# H05.net
KiCad netlist of a schematic drawn in EAGLE
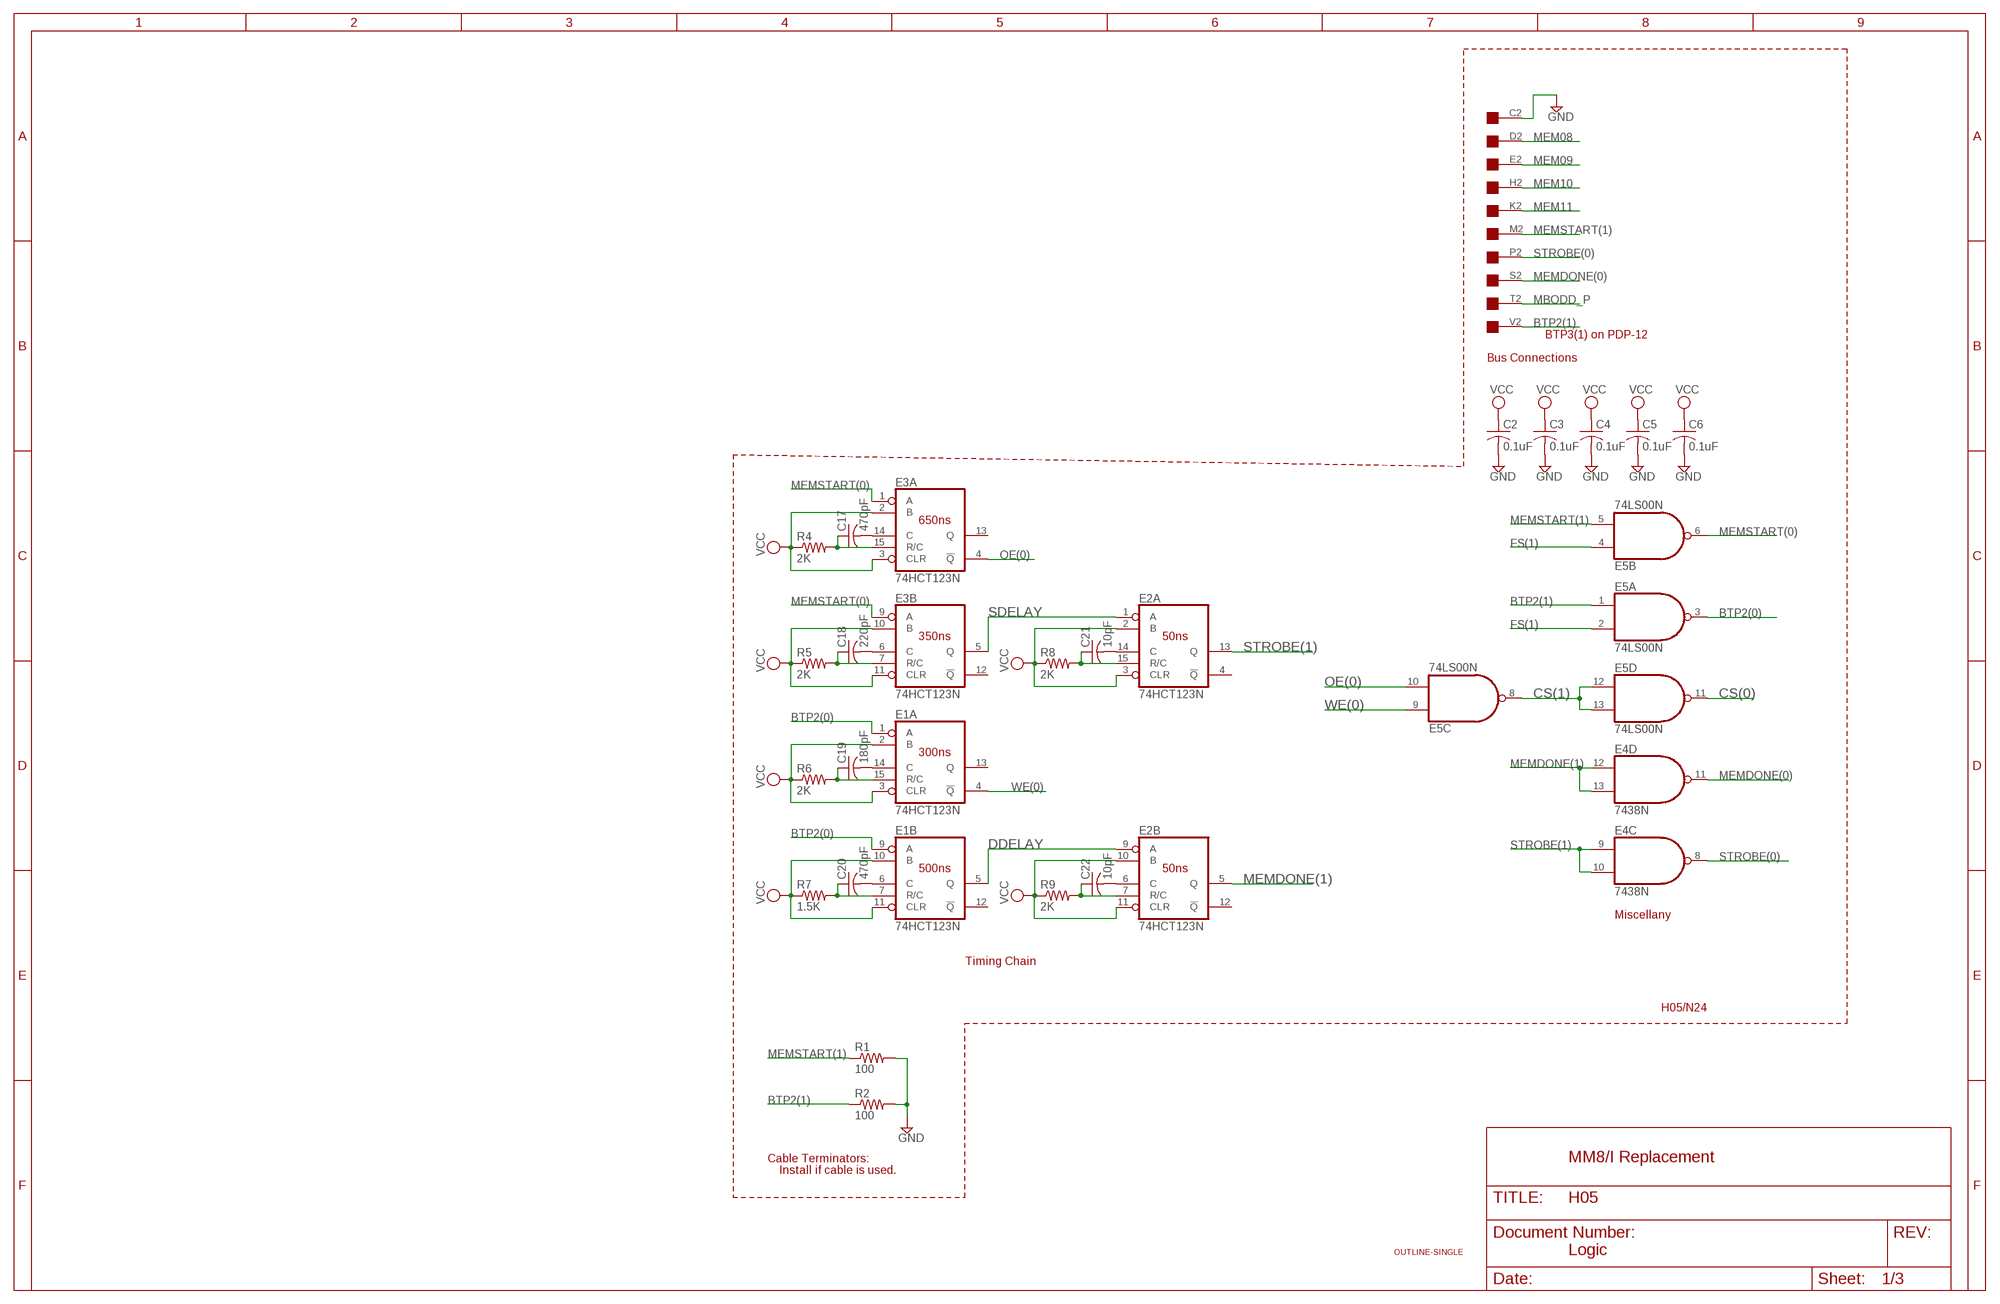
[diagram p0: schematic, sheet 1]
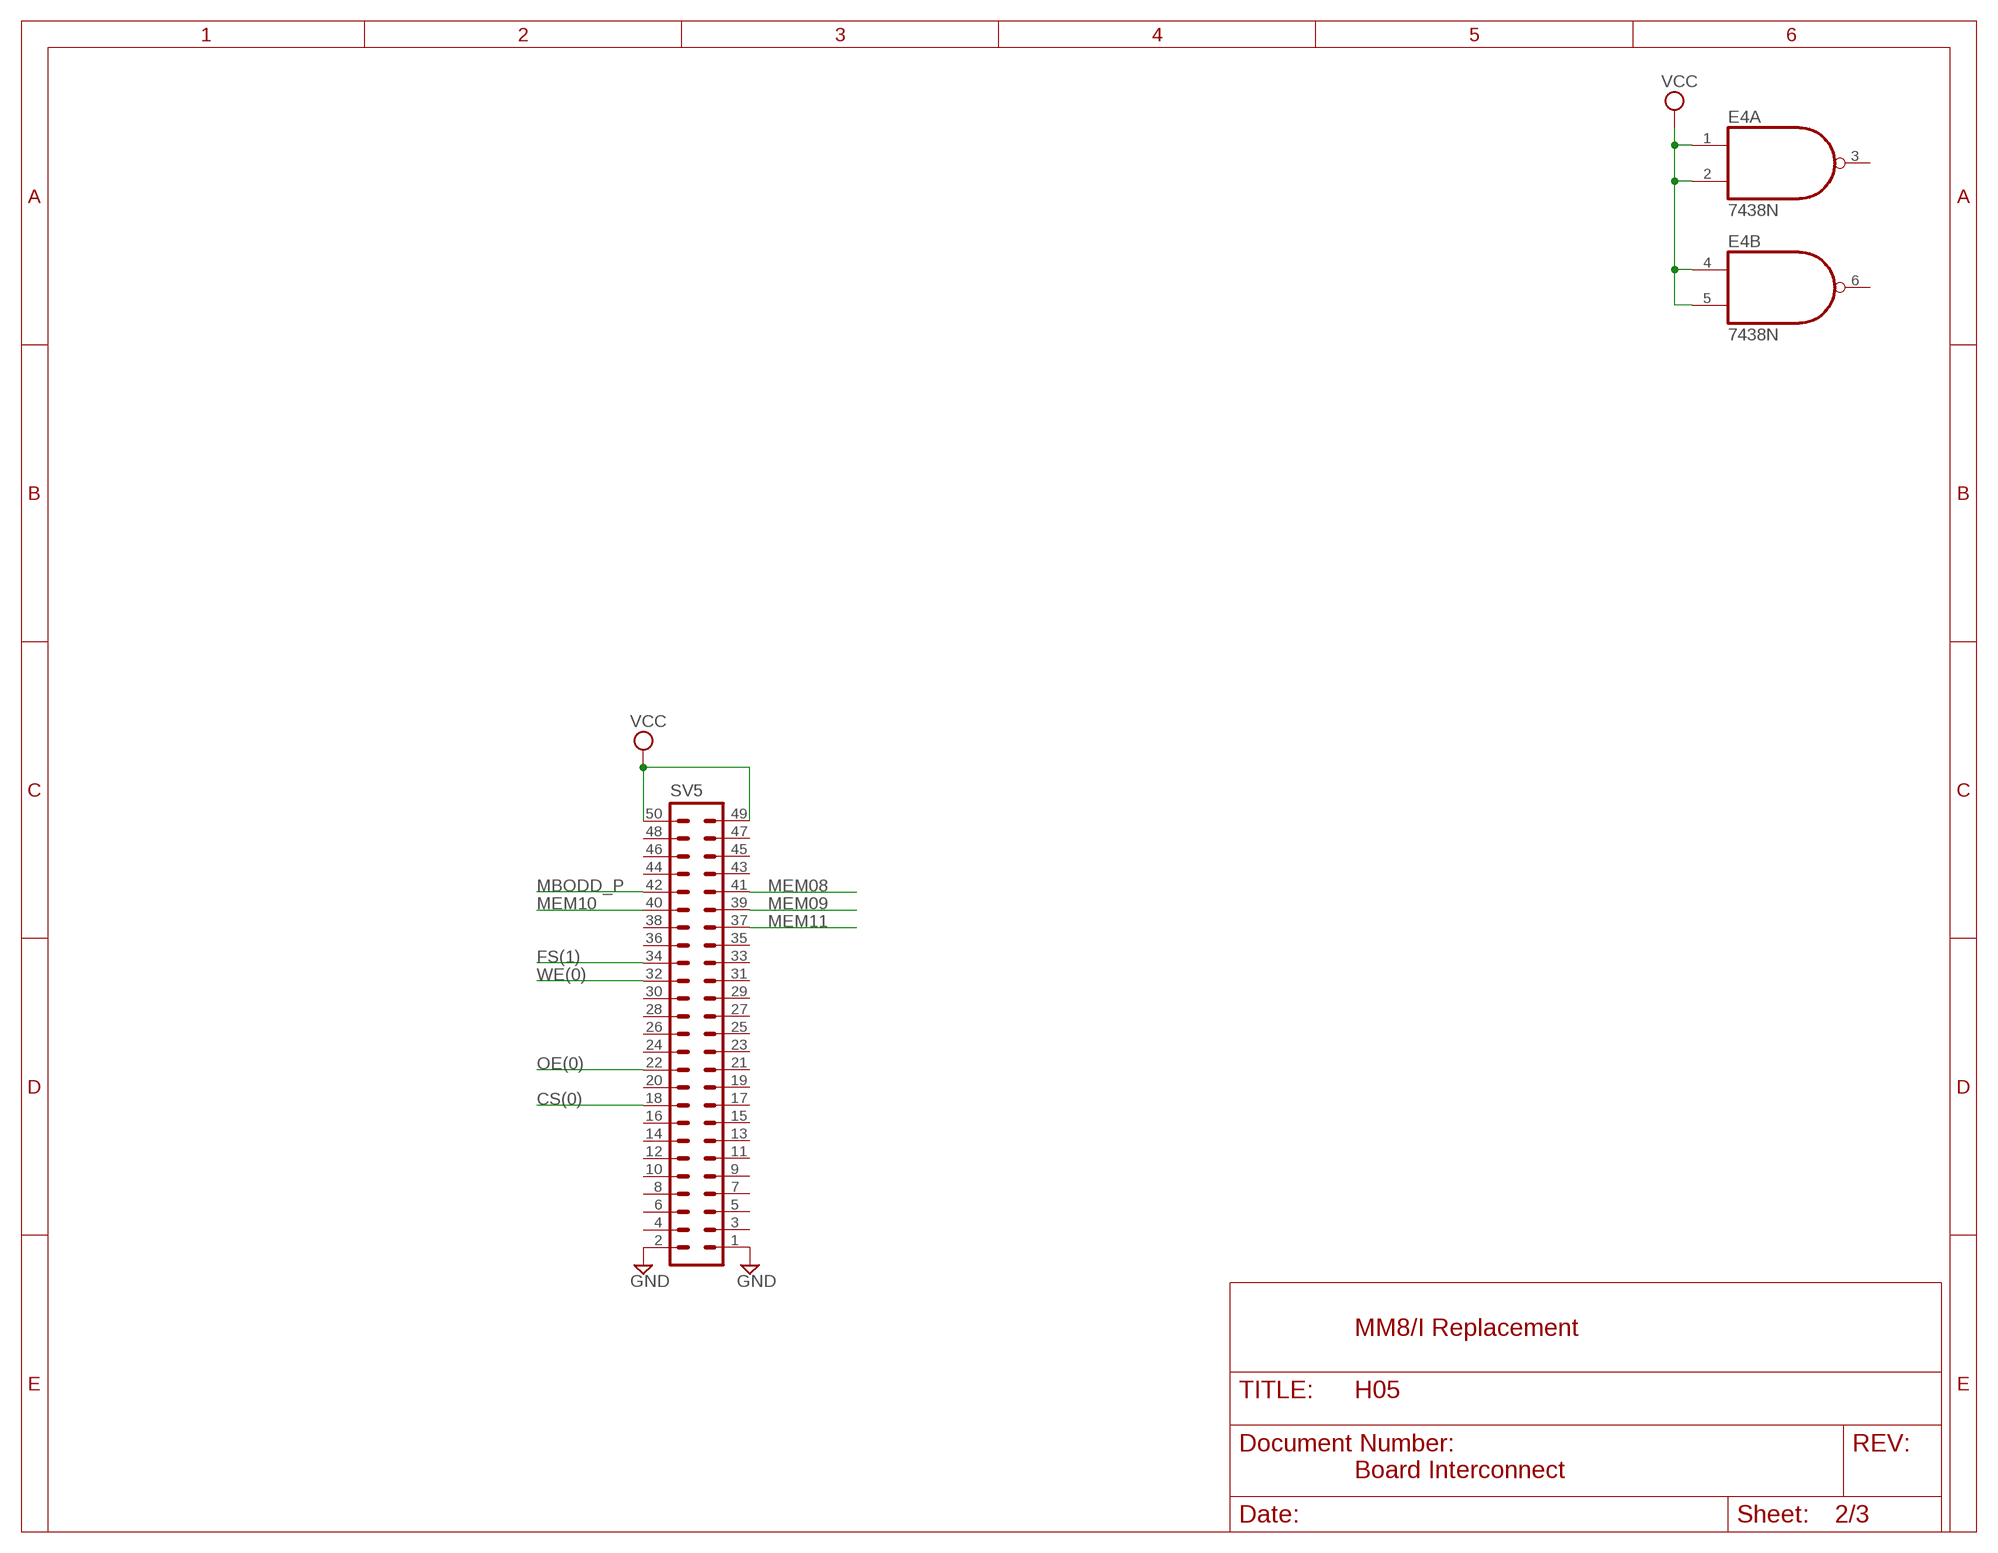
[diagram p1: schematic, sheet 2]
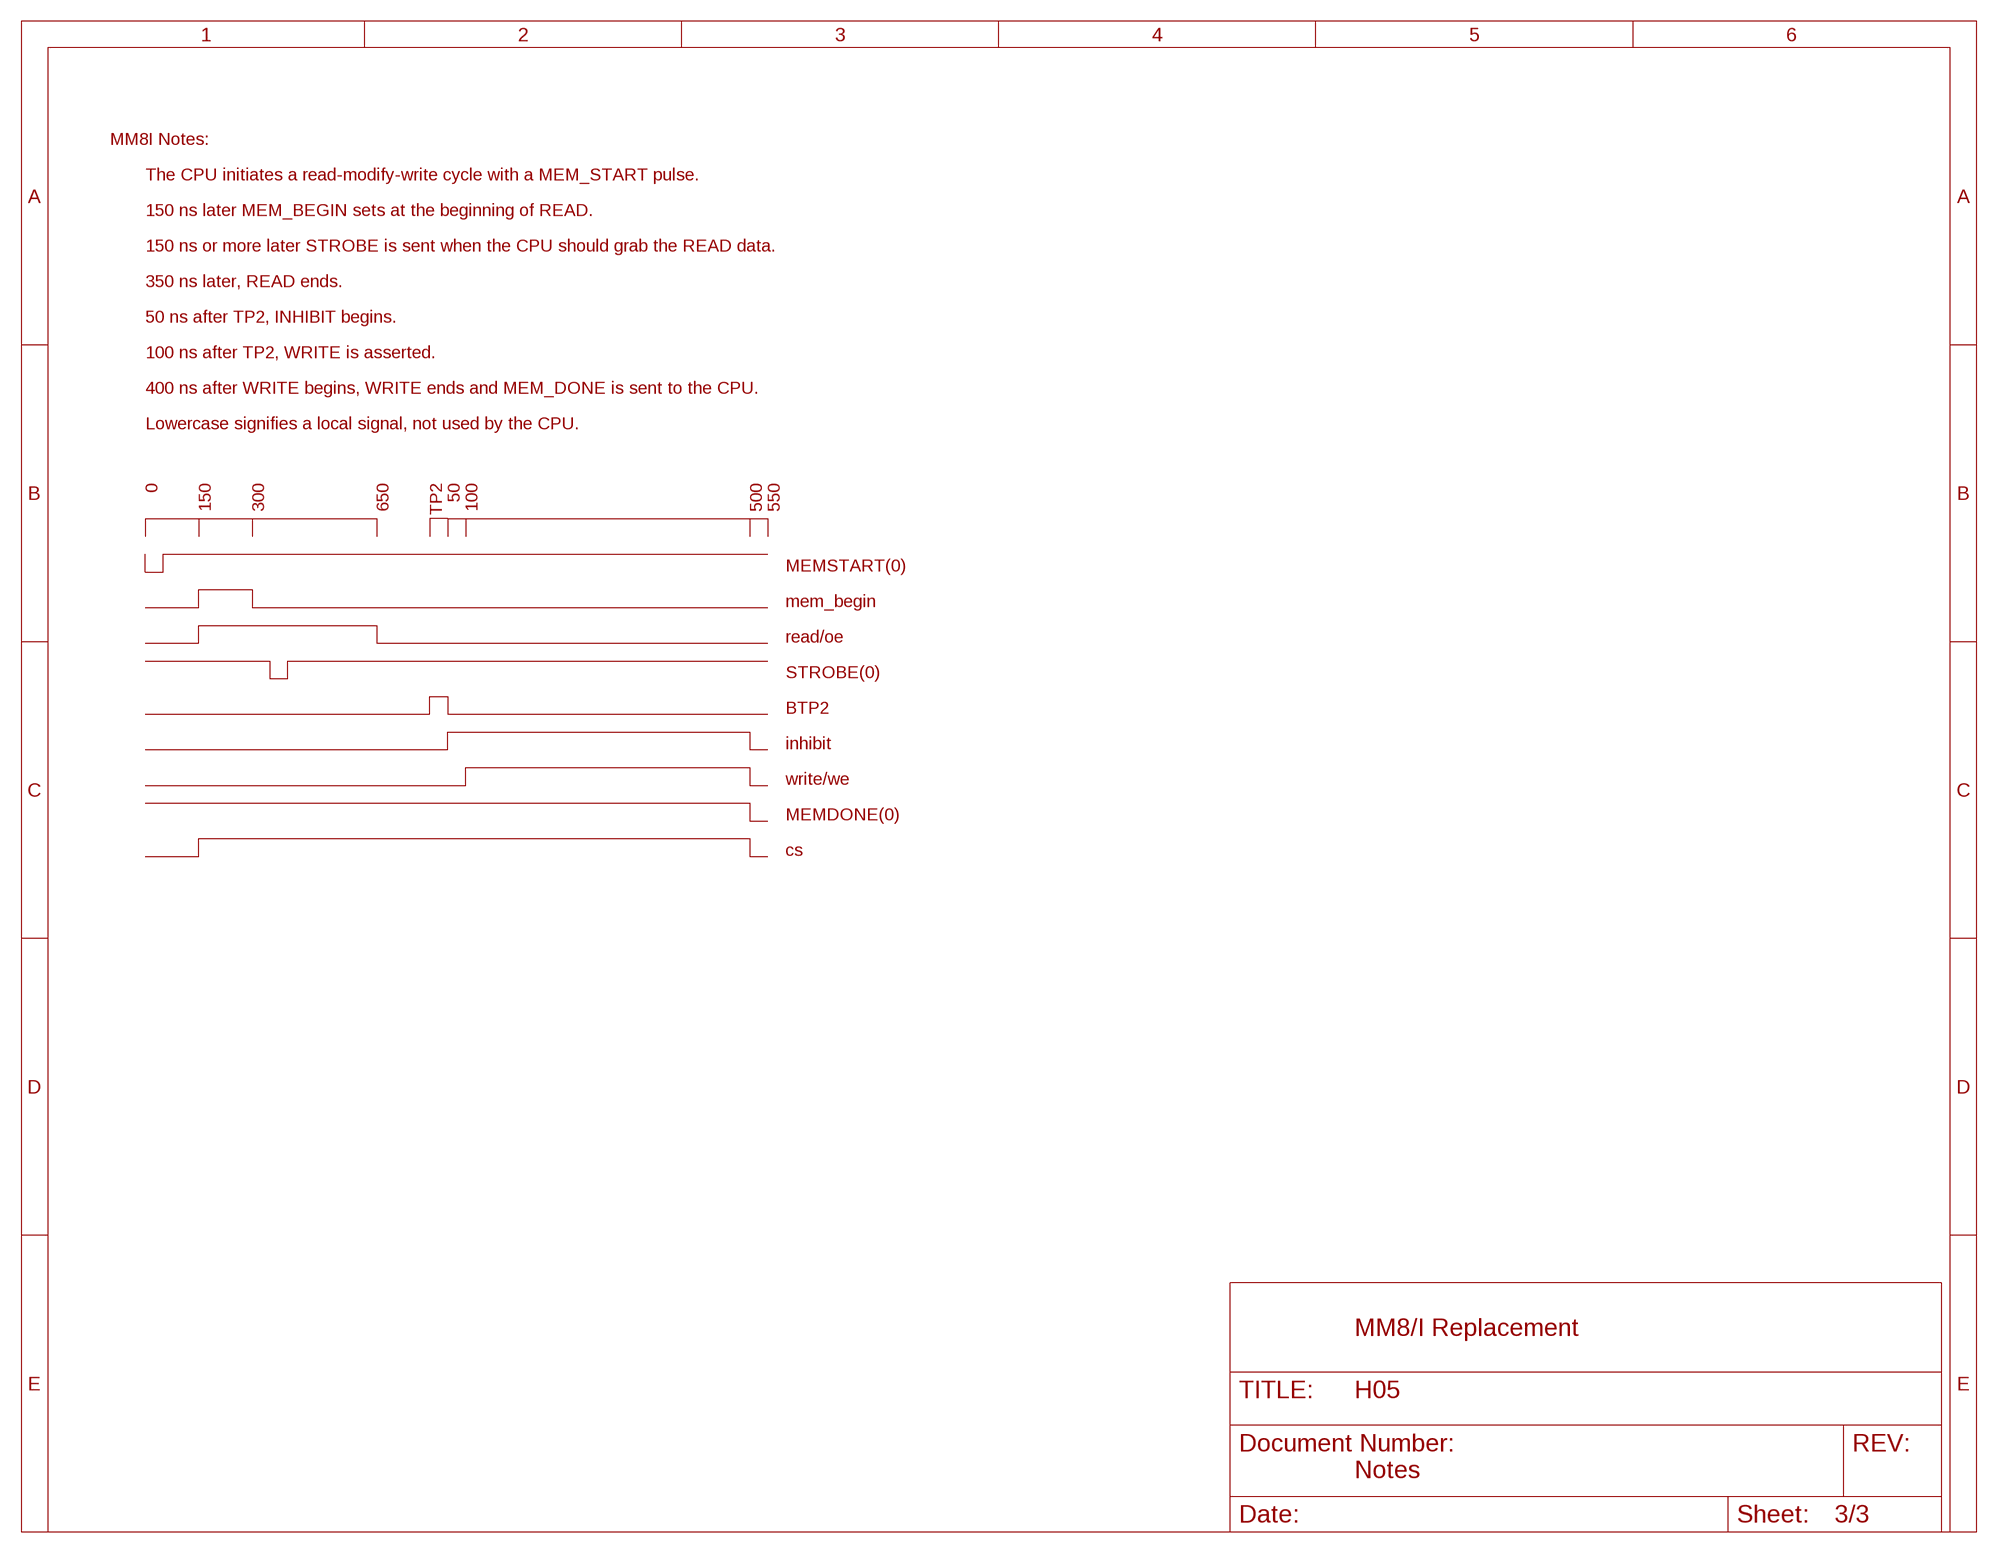
[diagram p2: schematic, sheet 3]

(export (version "E")
  (design (tool "Eeschema 10.0.6"))
  (components
    (comp (ref "C2")
      (value "0.1uF")
      (footprint "eagle-import:C050-025X075")
      (libsource (lib "eagle-import") (part "C-US050-025X075"))
    )
    (comp (ref "C3")
      (value "0.1uF")
      (footprint "eagle-import:C050-025X075")
      (libsource (lib "eagle-import") (part "C-US050-025X075"))
    )
    (comp (ref "C4")
      (value "0.1uF")
      (footprint "eagle-import:C050-025X075")
      (libsource (lib "eagle-import") (part "C-US050-025X075"))
    )
    (comp (ref "C5")
      (value "0.1uF")
      (footprint "eagle-import:C050-025X075")
      (libsource (lib "eagle-import") (part "C-US050-025X075"))
    )
    (comp (ref "C6")
      (value "0.1uF")
      (footprint "eagle-import:C050-025X075")
      (libsource (lib "eagle-import") (part "C-US050-025X075"))
    )
    (comp (ref "C17")
      (value "470pF")
      (footprint "eagle-import:C050-025X075")
      (libsource (lib "eagle-import") (part "C-US050-025X075"))
    )
    (comp (ref "C18")
      (value "220pF")
      (footprint "eagle-import:C050-025X075")
      (libsource (lib "eagle-import") (part "C-US050-025X075"))
    )
    (comp (ref "C19")
      (value "180pF")
      (footprint "eagle-import:C050-025X075")
      (libsource (lib "eagle-import") (part "C-US050-025X075"))
    )
    (comp (ref "C20")
      (value "470pF")
      (footprint "eagle-import:C050-025X075")
      (libsource (lib "eagle-import") (part "C-US050-025X075"))
    )
    (comp (ref "C21")
      (value "10pF")
      (footprint "eagle-import:C050-025X075")
      (libsource (lib "eagle-import") (part "C-US050-025X075"))
    )
    (comp (ref "C22")
      (value "10pF")
      (footprint "eagle-import:C050-025X075")
      (libsource (lib "eagle-import") (part "C-US050-025X075"))
    )
    (comp (ref "E1")
      (value "74HCT123N")
      (footprint "eagle-import:DIL16")
      (libsource (lib "eagle-import") (part "74123NLS"))
    )
    (comp (ref "E2")
      (value "74HCT123N")
      (footprint "eagle-import:DIL16")
      (libsource (lib "eagle-import") (part "74123NLS"))
    )
    (comp (ref "E3")
      (value "74HCT123N")
      (footprint "eagle-import:DIL16")
      (libsource (lib "eagle-import") (part "74123NLS"))
    )
    (comp (ref "E4")
      (value "7438N")
      (footprint "eagle-import:DIL14")
      (libsource (lib "eagle-import") (part "7438NLS"))
    )
    (comp (ref "E5")
      (value "74LS00N")
      (footprint "eagle-import:DIL14")
      (libsource (lib "eagle-import") (part "7400NLS"))
    )
    (comp (ref "H05")
      (value "EDGE-1")
      (footprint "eagle-import:EDGE-CON1")
      (libsource (lib "eagle-import") (part "EDGE-1"))
    )
    (comp (ref "R1")
      (value "100")
      (footprint "eagle-import:0207_10")
      (libsource (lib "eagle-import") (part "R-US_0207/10"))
    )
    (comp (ref "R2")
      (value "100")
      (footprint "eagle-import:0207_10")
      (libsource (lib "eagle-import") (part "R-US_0207/10"))
    )
    (comp (ref "R4")
      (value "2K")
      (footprint "eagle-import:0207_10")
      (libsource (lib "eagle-import") (part "R-US_0207/10"))
    )
    (comp (ref "R5")
      (value "2K")
      (footprint "eagle-import:0207_10")
      (libsource (lib "eagle-import") (part "R-US_0207/10"))
    )
    (comp (ref "R6")
      (value "2K")
      (footprint "eagle-import:0207_10")
      (libsource (lib "eagle-import") (part "R-US_0207/10"))
    )
    (comp (ref "R7")
      (value "1.5K")
      (footprint "eagle-import:0207_10")
      (libsource (lib "eagle-import") (part "R-US_0207/10"))
    )
    (comp (ref "R8")
      (value "2K")
      (footprint "eagle-import:0207_10")
      (libsource (lib "eagle-import") (part "R-US_0207/10"))
    )
    (comp (ref "R9")
      (value "2K")
      (footprint "eagle-import:0207_10")
      (libsource (lib "eagle-import") (part "R-US_0207/10"))
    )
    (comp (ref "U$1")
      (value "OUTLINE-SINGLE")
      (footprint "eagle-import:SINGLE")
      (libsource (lib "eagle-import") (part "OUTLINE-SINGLE"))
    )
    (comp (ref "SV5")
      (value "ML50L")
      (footprint "eagle-import:ML50L")
      (libsource (lib "eagle-import") (part "ML50L"))
    )
  )
  (nets
    (net (code "1") (name "BTP2(0)") (class "Default")
      (node (ref "E1") (pin "1") (pinfunction "A_1") (pintype "input"))
      (node (ref "E1") (pin "9") (pinfunction "A_9") (pintype "input"))
      (node (ref "E5") (pin "3") (pinfunction "O_3") (pintype "output"))
    )
    (net (code "2") (name "BTP2(1)") (class "Default")
      (node (ref "E5") (pin "1") (pinfunction "I0_1") (pintype "input"))
      (node (ref "H05") (pin "V2") (pinfunction "1_V2") (pintype "bidirectional"))
      (node (ref "R2") (pin "1") (pinfunction "1_1") (pintype "passive"))
    )
    (net (code "3") (name "CS(0)") (class "Default")
      (node (ref "E5") (pin "11") (pinfunction "O_11") (pintype "output"))
      (node (ref "SV5") (pin "18") (pinfunction "18_18") (pintype "passive"))
    )
    (net (code "4") (name "CS(1)") (class "Default")
      (node (ref "E5") (pin "12") (pinfunction "I0_12") (pintype "input"))
      (node (ref "E5") (pin "13") (pinfunction "I1_13") (pintype "input"))
      (node (ref "E5") (pin "8") (pinfunction "O_8") (pintype "output"))
    )
    (net (code "5") (name "DDELAY") (class "Default")
      (node (ref "E1") (pin "5") (pinfunction "Q_5") (pintype "output"))
      (node (ref "E2") (pin "9") (pinfunction "A_9") (pintype "input"))
    )
    (net (code "6") (name "FS(1)") (class "Default")
      (node (ref "E5") (pin "2") (pinfunction "I1_2") (pintype "input"))
      (node (ref "E5") (pin "4") (pinfunction "I0_4") (pintype "input"))
      (node (ref "SV5") (pin "34") (pinfunction "34_34") (pintype "passive"))
    )
    (net (code "7") (name "GND") (class "Default")
      (node (ref "C2") (pin "2") (pinfunction "2_2") (pintype "passive"))
      (node (ref "C3") (pin "2") (pinfunction "2_2") (pintype "passive"))
      (node (ref "C4") (pin "2") (pinfunction "2_2") (pintype "passive"))
      (node (ref "C5") (pin "2") (pinfunction "2_2") (pintype "passive"))
      (node (ref "C6") (pin "2") (pinfunction "2_2") (pintype "passive"))
      (node (ref "H05") (pin "C2") (pinfunction "1_C2") (pintype "bidirectional"))
      (node (ref "R1") (pin "2") (pinfunction "2_2") (pintype "passive"))
      (node (ref "R2") (pin "2") (pinfunction "2_2") (pintype "passive"))
      (node (ref "SV5") (pin "1") (pinfunction "1_1") (pintype "passive"))
      (node (ref "SV5") (pin "2") (pinfunction "2_2") (pintype "passive"))
    )
    (net (code "8") (name "MBODD_P") (class "Default")
      (node (ref "H05") (pin "T2") (pinfunction "1_T2") (pintype "bidirectional"))
      (node (ref "SV5") (pin "42") (pinfunction "42_42") (pintype "passive"))
    )
    (net (code "9") (name "MEM08") (class "Default")
      (node (ref "H05") (pin "D2") (pinfunction "1_D2") (pintype "bidirectional"))
      (node (ref "SV5") (pin "41") (pinfunction "41_41") (pintype "passive"))
    )
    (net (code "10") (name "MEM09") (class "Default")
      (node (ref "H05") (pin "E2") (pinfunction "1_E2") (pintype "bidirectional"))
      (node (ref "SV5") (pin "39") (pinfunction "39_39") (pintype "passive"))
    )
    (net (code "11") (name "MEM10") (class "Default")
      (node (ref "H05") (pin "H2") (pinfunction "1_H2") (pintype "bidirectional"))
      (node (ref "SV5") (pin "40") (pinfunction "40_40") (pintype "passive"))
    )
    (net (code "12") (name "MEM11") (class "Default")
      (node (ref "H05") (pin "K2") (pinfunction "1_K2") (pintype "bidirectional"))
      (node (ref "SV5") (pin "37") (pinfunction "37_37") (pintype "passive"))
    )
    (net (code "13") (name "MEMDONE(0)") (class "Default")
      (node (ref "E4") (pin "11") (pinfunction "O_11") (pintype "open_collector"))
      (node (ref "H05") (pin "S2") (pinfunction "1_S2") (pintype "bidirectional"))
    )
    (net (code "14") (name "MEMDONE(1)") (class "Default")
      (node (ref "E2") (pin "5") (pinfunction "Q_5") (pintype "output"))
      (node (ref "E4") (pin "12") (pinfunction "I0_12") (pintype "input"))
      (node (ref "E4") (pin "13") (pinfunction "I1_13") (pintype "input"))
    )
    (net (code "15") (name "MEMSTART(0)") (class "Default")
      (node (ref "E3") (pin "1") (pinfunction "A_1") (pintype "input"))
      (node (ref "E3") (pin "9") (pinfunction "A_9") (pintype "input"))
      (node (ref "E5") (pin "6") (pinfunction "O_6") (pintype "output"))
    )
    (net (code "16") (name "MEMSTART(1)") (class "Default")
      (node (ref "E5") (pin "5") (pinfunction "I1_5") (pintype "input"))
      (node (ref "H05") (pin "M2") (pinfunction "1_M2") (pintype "bidirectional"))
      (node (ref "R1") (pin "1") (pinfunction "1_1") (pintype "passive"))
    )
    (net (code "17") (name "Net-(E1A-C)") (class "Default")
      (node (ref "C19") (pin "2") (pinfunction "2_2") (pintype "passive"))
      (node (ref "E1") (pin "14") (pinfunction "C_14") (pintype "input"))
    )
    (net (code "18") (name "Net-(E1A-R{slash}C)") (class "Default")
      (node (ref "C19") (pin "1") (pinfunction "1_1") (pintype "passive"))
      (node (ref "E1") (pin "15") (pinfunction "R/C_15") (pintype "input"))
      (node (ref "R6") (pin "2") (pinfunction "2_2") (pintype "passive"))
    )
    (net (code "19") (name "Net-(E1B-C)") (class "Default")
      (node (ref "C20") (pin "2") (pinfunction "2_2") (pintype "passive"))
      (node (ref "E1") (pin "6") (pinfunction "C_6") (pintype "input"))
    )
    (net (code "20") (name "Net-(E1B-R{slash}C)") (class "Default")
      (node (ref "C20") (pin "1") (pinfunction "1_1") (pintype "passive"))
      (node (ref "E1") (pin "7") (pinfunction "R/C_7") (pintype "input"))
      (node (ref "R7") (pin "2") (pinfunction "2_2") (pintype "passive"))
    )
    (net (code "21") (name "Net-(E2A-C)") (class "Default")
      (node (ref "C21") (pin "2") (pinfunction "2_2") (pintype "passive"))
      (node (ref "E2") (pin "14") (pinfunction "C_14") (pintype "input"))
    )
    (net (code "22") (name "Net-(E2A-R{slash}C)") (class "Default")
      (node (ref "C21") (pin "1") (pinfunction "1_1") (pintype "passive"))
      (node (ref "E2") (pin "15") (pinfunction "R/C_15") (pintype "input"))
      (node (ref "R8") (pin "2") (pinfunction "2_2") (pintype "passive"))
    )
    (net (code "23") (name "Net-(E2B-C)") (class "Default")
      (node (ref "C22") (pin "2") (pinfunction "2_2") (pintype "passive"))
      (node (ref "E2") (pin "6") (pinfunction "C_6") (pintype "input"))
    )
    (net (code "24") (name "Net-(E2B-R{slash}C)") (class "Default")
      (node (ref "C22") (pin "1") (pinfunction "1_1") (pintype "passive"))
      (node (ref "E2") (pin "7") (pinfunction "R/C_7") (pintype "input"))
      (node (ref "R9") (pin "2") (pinfunction "2_2") (pintype "passive"))
    )
    (net (code "25") (name "Net-(E3A-C)") (class "Default")
      (node (ref "C17") (pin "2") (pinfunction "2_2") (pintype "passive"))
      (node (ref "E3") (pin "14") (pinfunction "C_14") (pintype "input"))
    )
    (net (code "26") (name "Net-(E3A-R{slash}C)") (class "Default")
      (node (ref "C17") (pin "1") (pinfunction "1_1") (pintype "passive"))
      (node (ref "E3") (pin "15") (pinfunction "R/C_15") (pintype "input"))
      (node (ref "R4") (pin "2") (pinfunction "2_2") (pintype "passive"))
    )
    (net (code "27") (name "Net-(E3B-C)") (class "Default")
      (node (ref "C18") (pin "2") (pinfunction "2_2") (pintype "passive"))
      (node (ref "E3") (pin "6") (pinfunction "C_6") (pintype "input"))
    )
    (net (code "28") (name "Net-(E3B-R{slash}C)") (class "Default")
      (node (ref "C18") (pin "1") (pinfunction "1_1") (pintype "passive"))
      (node (ref "E3") (pin "7") (pinfunction "R/C_7") (pintype "input"))
      (node (ref "R5") (pin "2") (pinfunction "2_2") (pintype "passive"))
    )
    (net (code "29") (name "OE(0)") (class "Default")
      (node (ref "E3") (pin "4") (pinfunction "~{Q}_4") (pintype "output"))
      (node (ref "E5") (pin "10") (pinfunction "I1_10") (pintype "input"))
      (node (ref "SV5") (pin "22") (pinfunction "22_22") (pintype "passive"))
    )
    (net (code "30") (name "SDELAY") (class "Default")
      (node (ref "E2") (pin "1") (pinfunction "A_1") (pintype "input"))
      (node (ref "E3") (pin "5") (pinfunction "Q_5") (pintype "output"))
    )
    (net (code "31") (name "STROBE(0)") (class "Default")
      (node (ref "E4") (pin "8") (pinfunction "O_8") (pintype "open_collector"))
      (node (ref "H05") (pin "P2") (pinfunction "1_P2") (pintype "bidirectional"))
    )
    (net (code "32") (name "STROBE(1)") (class "Default")
      (node (ref "E2") (pin "13") (pinfunction "Q_13") (pintype "output"))
      (node (ref "E4") (pin "10") (pinfunction "I1_10") (pintype "input"))
      (node (ref "E4") (pin "9") (pinfunction "I0_9") (pintype "input"))
    )
    (net (code "33") (name "VCC") (class "Default")
      (node (ref "C2") (pin "1") (pinfunction "1_1") (pintype "passive"))
      (node (ref "C3") (pin "1") (pinfunction "1_1") (pintype "passive"))
      (node (ref "C4") (pin "1") (pinfunction "1_1") (pintype "passive"))
      (node (ref "C5") (pin "1") (pinfunction "1_1") (pintype "passive"))
      (node (ref "C6") (pin "1") (pinfunction "1_1") (pintype "passive"))
      (node (ref "E1") (pin "10") (pinfunction "B_10") (pintype "input"))
      (node (ref "E1") (pin "11") (pinfunction "CLR_11") (pintype "input"))
      (node (ref "E1") (pin "2") (pinfunction "B_2") (pintype "input"))
      (node (ref "E1") (pin "3") (pinfunction "CLR_3") (pintype "input"))
      (node (ref "E2") (pin "10") (pinfunction "B_10") (pintype "input"))
      (node (ref "E2") (pin "11") (pinfunction "CLR_11") (pintype "input"))
      (node (ref "E2") (pin "2") (pinfunction "B_2") (pintype "input"))
      (node (ref "E2") (pin "3") (pinfunction "CLR_3") (pintype "input"))
      (node (ref "E3") (pin "10") (pinfunction "B_10") (pintype "input"))
      (node (ref "E3") (pin "11") (pinfunction "CLR_11") (pintype "input"))
      (node (ref "E3") (pin "2") (pinfunction "B_2") (pintype "input"))
      (node (ref "E3") (pin "3") (pinfunction "CLR_3") (pintype "input"))
      (node (ref "E4") (pin "1") (pinfunction "I0_1") (pintype "input"))
      (node (ref "E4") (pin "2") (pinfunction "I1_2") (pintype "input"))
      (node (ref "E4") (pin "4") (pinfunction "I0_4") (pintype "input"))
      (node (ref "E4") (pin "5") (pinfunction "I1_5") (pintype "input"))
      (node (ref "R4") (pin "1") (pinfunction "1_1") (pintype "passive"))
      (node (ref "R5") (pin "1") (pinfunction "1_1") (pintype "passive"))
      (node (ref "R6") (pin "1") (pinfunction "1_1") (pintype "passive"))
      (node (ref "R7") (pin "1") (pinfunction "1_1") (pintype "passive"))
      (node (ref "R8") (pin "1") (pinfunction "1_1") (pintype "passive"))
      (node (ref "R9") (pin "1") (pinfunction "1_1") (pintype "passive"))
      (node (ref "SV5") (pin "49") (pinfunction "49_49") (pintype "passive"))
      (node (ref "SV5") (pin "50") (pinfunction "50_50") (pintype "passive"))
    )
    (net (code "34") (name "WE(0)") (class "Default")
      (node (ref "E1") (pin "4") (pinfunction "~{Q}_4") (pintype "output"))
      (node (ref "E5") (pin "9") (pinfunction "I0_9") (pintype "input"))
      (node (ref "SV5") (pin "32") (pinfunction "32_32") (pintype "passive"))
    )
    (net (code "35") (name "unconnected-(E1A-Q-Pad13)") (class "Default")
      (node (ref "E1") (pin "13") (pinfunction "Q_13") (pintype "output"))
    )
    (net (code "36") (name "unconnected-(E1B-~{Q}-Pad12)") (class "Default")
      (node (ref "E1") (pin "12") (pinfunction "~{Q}_12") (pintype "output"))
    )
    (net (code "37") (name "unconnected-(E2A-~{Q}-Pad4)") (class "Default")
      (node (ref "E2") (pin "4") (pinfunction "~{Q}_4") (pintype "output"))
    )
    (net (code "38") (name "unconnected-(E2B-~{Q}-Pad12)") (class "Default")
      (node (ref "E2") (pin "12") (pinfunction "~{Q}_12") (pintype "output"))
    )
    (net (code "39") (name "unconnected-(E3A-Q-Pad13)") (class "Default")
      (node (ref "E3") (pin "13") (pinfunction "Q_13") (pintype "output"))
    )
    (net (code "40") (name "unconnected-(E3B-~{Q}-Pad12)") (class "Default")
      (node (ref "E3") (pin "12") (pinfunction "~{Q}_12") (pintype "output"))
    )
    (net (code "41") (name "unconnected-(E4A-O-Pad3)") (class "Default")
      (node (ref "E4") (pin "3") (pinfunction "O_3") (pintype "open_collector"))
    )
    (net (code "42") (name "unconnected-(E4B-O-Pad6)") (class "Default")
      (node (ref "E4") (pin "6") (pinfunction "O_6") (pintype "open_collector"))
    )
    (net (code "43") (name "unconnected-(SV5-Pad3)") (class "Default")
      (node (ref "SV5") (pin "3") (pinfunction "3_3") (pintype "passive"))
    )
    (net (code "44") (name "unconnected-(SV5-Pad4)") (class "Default")
      (node (ref "SV5") (pin "4") (pinfunction "4_4") (pintype "passive"))
    )
    (net (code "45") (name "unconnected-(SV5-Pad5)") (class "Default")
      (node (ref "SV5") (pin "5") (pinfunction "5_5") (pintype "passive"))
    )
    (net (code "46") (name "unconnected-(SV5-Pad6)") (class "Default")
      (node (ref "SV5") (pin "6") (pinfunction "6_6") (pintype "passive"))
    )
    (net (code "47") (name "unconnected-(SV5-Pad7)") (class "Default")
      (node (ref "SV5") (pin "7") (pinfunction "7_7") (pintype "passive"))
    )
    (net (code "48") (name "unconnected-(SV5-Pad8)") (class "Default")
      (node (ref "SV5") (pin "8") (pinfunction "8_8") (pintype "passive"))
    )
    (net (code "49") (name "unconnected-(SV5-Pad9)") (class "Default")
      (node (ref "SV5") (pin "9") (pinfunction "9_9") (pintype "passive"))
    )
    (net (code "50") (name "unconnected-(SV5-Pad10)") (class "Default")
      (node (ref "SV5") (pin "10") (pinfunction "10_10") (pintype "passive"))
    )
    (net (code "51") (name "unconnected-(SV5-Pad11)") (class "Default")
      (node (ref "SV5") (pin "11") (pinfunction "11_11") (pintype "passive"))
    )
    (net (code "52") (name "unconnected-(SV5-Pad12)") (class "Default")
      (node (ref "SV5") (pin "12") (pinfunction "12_12") (pintype "passive"))
    )
    (net (code "53") (name "unconnected-(SV5-Pad13)") (class "Default")
      (node (ref "SV5") (pin "13") (pinfunction "13_13") (pintype "passive"))
    )
    (net (code "54") (name "unconnected-(SV5-Pad14)") (class "Default")
      (node (ref "SV5") (pin "14") (pinfunction "14_14") (pintype "passive"))
    )
    (net (code "55") (name "unconnected-(SV5-Pad15)") (class "Default")
      (node (ref "SV5") (pin "15") (pinfunction "15_15") (pintype "passive"))
    )
    (net (code "56") (name "unconnected-(SV5-Pad16)") (class "Default")
      (node (ref "SV5") (pin "16") (pinfunction "16_16") (pintype "passive"))
    )
    (net (code "57") (name "unconnected-(SV5-Pad17)") (class "Default")
      (node (ref "SV5") (pin "17") (pinfunction "17_17") (pintype "passive"))
    )
    (net (code "58") (name "unconnected-(SV5-Pad19)") (class "Default")
      (node (ref "SV5") (pin "19") (pinfunction "19_19") (pintype "passive"))
    )
    (net (code "59") (name "unconnected-(SV5-Pad20)") (class "Default")
      (node (ref "SV5") (pin "20") (pinfunction "20_20") (pintype "passive"))
    )
    (net (code "60") (name "unconnected-(SV5-Pad21)") (class "Default")
      (node (ref "SV5") (pin "21") (pinfunction "21_21") (pintype "passive"))
    )
    (net (code "61") (name "unconnected-(SV5-Pad23)") (class "Default")
      (node (ref "SV5") (pin "23") (pinfunction "23_23") (pintype "passive"))
    )
    (net (code "62") (name "unconnected-(SV5-Pad24)") (class "Default")
      (node (ref "SV5") (pin "24") (pinfunction "24_24") (pintype "passive"))
    )
    (net (code "63") (name "unconnected-(SV5-Pad25)") (class "Default")
      (node (ref "SV5") (pin "25") (pinfunction "25_25") (pintype "passive"))
    )
    (net (code "64") (name "unconnected-(SV5-Pad26)") (class "Default")
      (node (ref "SV5") (pin "26") (pinfunction "26_26") (pintype "passive"))
    )
    (net (code "65") (name "unconnected-(SV5-Pad27)") (class "Default")
      (node (ref "SV5") (pin "27") (pinfunction "27_27") (pintype "passive"))
    )
    (net (code "66") (name "unconnected-(SV5-Pad28)") (class "Default")
      (node (ref "SV5") (pin "28") (pinfunction "28_28") (pintype "passive"))
    )
    (net (code "67") (name "unconnected-(SV5-Pad29)") (class "Default")
      (node (ref "SV5") (pin "29") (pinfunction "29_29") (pintype "passive"))
    )
    (net (code "68") (name "unconnected-(SV5-Pad30)") (class "Default")
      (node (ref "SV5") (pin "30") (pinfunction "30_30") (pintype "passive"))
    )
    (net (code "69") (name "unconnected-(SV5-Pad31)") (class "Default")
      (node (ref "SV5") (pin "31") (pinfunction "31_31") (pintype "passive"))
    )
    (net (code "70") (name "unconnected-(SV5-Pad33)") (class "Default")
      (node (ref "SV5") (pin "33") (pinfunction "33_33") (pintype "passive"))
    )
    (net (code "71") (name "unconnected-(SV5-Pad35)") (class "Default")
      (node (ref "SV5") (pin "35") (pinfunction "35_35") (pintype "passive"))
    )
    (net (code "72") (name "unconnected-(SV5-Pad36)") (class "Default")
      (node (ref "SV5") (pin "36") (pinfunction "36_36") (pintype "passive"))
    )
    (net (code "73") (name "unconnected-(SV5-Pad38)") (class "Default")
      (node (ref "SV5") (pin "38") (pinfunction "38_38") (pintype "passive"))
    )
    (net (code "74") (name "unconnected-(SV5-Pad43)") (class "Default")
      (node (ref "SV5") (pin "43") (pinfunction "43_43") (pintype "passive"))
    )
    (net (code "75") (name "unconnected-(SV5-Pad44)") (class "Default")
      (node (ref "SV5") (pin "44") (pinfunction "44_44") (pintype "passive"))
    )
    (net (code "76") (name "unconnected-(SV5-Pad45)") (class "Default")
      (node (ref "SV5") (pin "45") (pinfunction "45_45") (pintype "passive"))
    )
    (net (code "77") (name "unconnected-(SV5-Pad46)") (class "Default")
      (node (ref "SV5") (pin "46") (pinfunction "46_46") (pintype "passive"))
    )
    (net (code "78") (name "unconnected-(SV5-Pad47)") (class "Default")
      (node (ref "SV5") (pin "47") (pinfunction "47_47") (pintype "passive"))
    )
    (net (code "79") (name "unconnected-(SV5-Pad48)") (class "Default")
      (node (ref "SV5") (pin "48") (pinfunction "48_48") (pintype "passive"))
    )
  )
)
